# pcb_pedale_test-H743-TLV320AIC23B.net
KiCad netlist of a schematic drawn in EAGLE
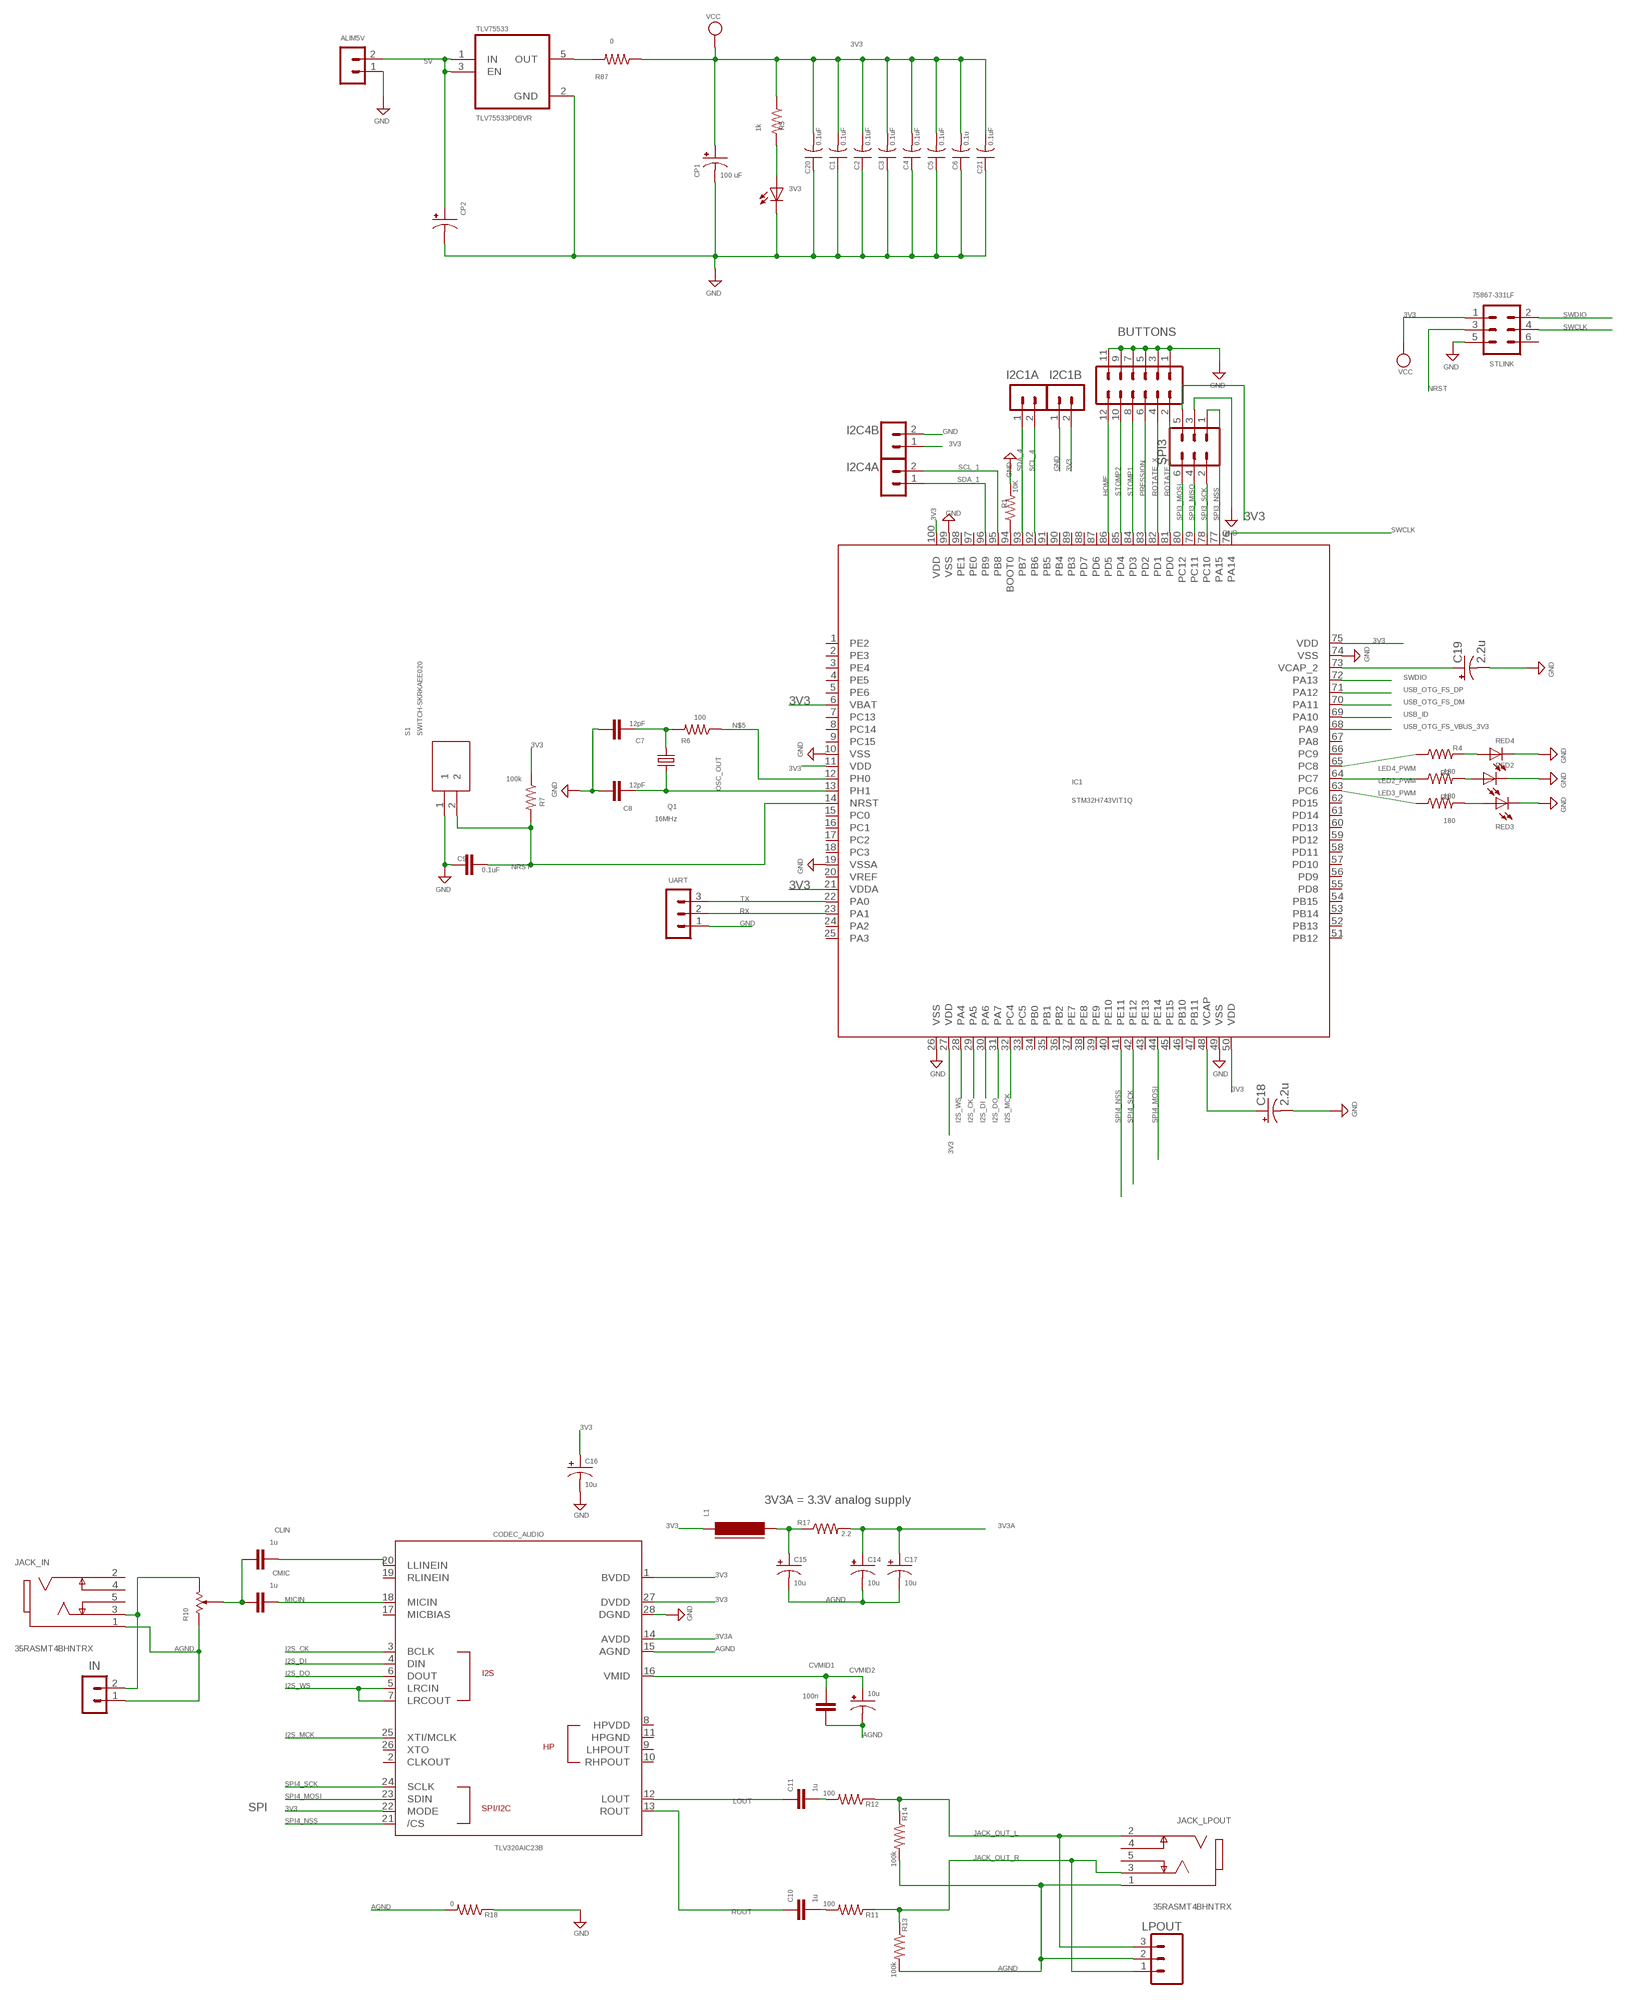
[diagram p0: schematic, sheet 1, part 1 of 2]
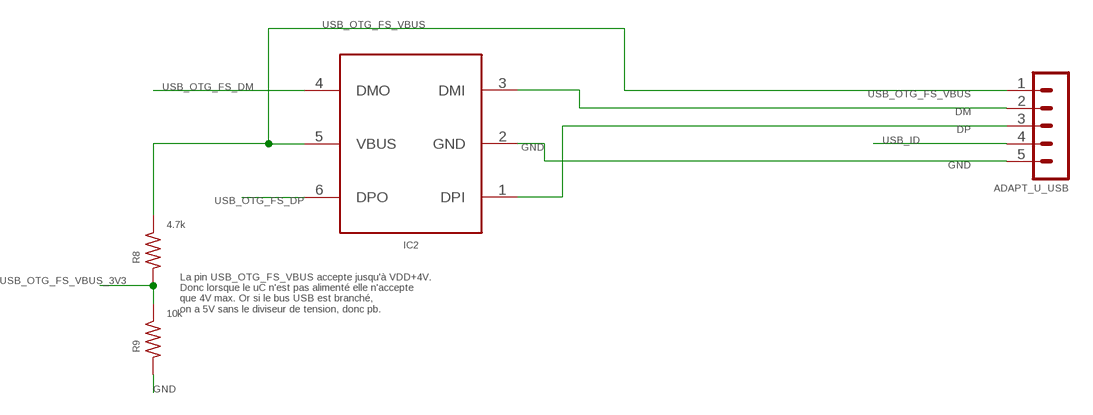
[diagram p1: schematic, sheet 1, part 2 of 2]

(export (version "E")
  (design (tool "Eeschema 10.0.6"))
  (components
    (comp (ref "3V3")
      (value "LED-0805")
      (footprint "eagle-import:0805-LED")
      (libsource (lib "eagle-import") (part "LED-0805"))
    )
    (comp (ref "ADAPT_U_USB")
      (value "MA05-1")
      (footprint "eagle-import:MA05-1")
      (libsource (lib "eagle-import") (part "MA05-1"))
    )
    (comp (ref "ALIM5V")
      (value "MA02-1")
      (footprint "eagle-import:MA02-1")
      (libsource (lib "eagle-import") (part "MA02-1"))
    )
    (comp (ref "BUTTONS")
      (value "MA06-2")
      (footprint "eagle-import:MA06-2")
      (libsource (lib "eagle-import") (part "MA06-2"))
    )
    (comp (ref "C1")
      (value "0.1uF")
      (footprint "eagle-import:C0805")
      (libsource (lib "eagle-import") (part "C-US0805"))
    )
    (comp (ref "C2")
      (value "0.1uF")
      (footprint "eagle-import:C0805")
      (libsource (lib "eagle-import") (part "C-US0805"))
    )
    (comp (ref "C3")
      (value "0.1uF")
      (footprint "eagle-import:C0805")
      (libsource (lib "eagle-import") (part "C-US0805"))
    )
    (comp (ref "C4")
      (value "0.1uF")
      (footprint "eagle-import:C0805")
      (libsource (lib "eagle-import") (part "C-US0805"))
    )
    (comp (ref "C5")
      (value "0.1uF")
      (footprint "eagle-import:C0805")
      (libsource (lib "eagle-import") (part "C-US0805"))
    )
    (comp (ref "C6")
      (value "0.1u")
      (footprint "eagle-import:C0805")
      (libsource (lib "eagle-import") (part "C-US0805"))
    )
    (comp (ref "C7")
      (value "12pF")
      (footprint "eagle-import:1206")
      (libsource (lib "eagle-import") (part "PASSIF-CAP-1206"))
    )
    (comp (ref "C8")
      (value "12pF")
      (footprint "eagle-import:1206")
      (libsource (lib "eagle-import") (part "PASSIF-CAP-1206"))
    )
    (comp (ref "C9")
      (value "0.1uF")
      (footprint "eagle-import:1206")
      (libsource (lib "eagle-import") (part "PASSIF-CAP-1206"))
    )
    (comp (ref "C10")
      (value "1u")
      (footprint "eagle-import:1206")
      (libsource (lib "eagle-import") (part "PASSIF-CAP-1206"))
    )
    (comp (ref "C11")
      (value "1u")
      (footprint "eagle-import:1206")
      (libsource (lib "eagle-import") (part "PASSIF-CAP-1206"))
    )
    (comp (ref "C14")
      (value "10u")
      (footprint "eagle-import:CPOL2917")
      (libsource (lib "eagle-import") (part "PASSIF-CPOL-US2917"))
    )
    (comp (ref "C15")
      (value "10u")
      (footprint "eagle-import:CPOL2917")
      (libsource (lib "eagle-import") (part "PASSIF-CPOL-US2917"))
    )
    (comp (ref "C16")
      (value "10u")
      (footprint "eagle-import:CPOL2917")
      (libsource (lib "eagle-import") (part "PASSIF-CPOL-US2917"))
    )
    (comp (ref "C17")
      (value "10u")
      (footprint "eagle-import:CPOL2917")
      (libsource (lib "eagle-import") (part "PASSIF-CPOL-US2917"))
    )
    (comp (ref "C18")
      (value "2.2u")
      (footprint "eagle-import:CPOL0805")
      (libsource (lib "eagle-import") (part "PASSIF-CPOL-US0805"))
    )
    (comp (ref "C19")
      (value "2.2u")
      (footprint "eagle-import:CPOL0805")
      (libsource (lib "eagle-import") (part "PASSIF-CPOL-US0805"))
    )
    (comp (ref "C20")
      (value "0.1uF")
      (footprint "eagle-import:C0805")
      (libsource (lib "eagle-import") (part "C-US0805"))
    )
    (comp (ref "C21")
      (value "0.1uF")
      (footprint "eagle-import:C0805")
      (libsource (lib "eagle-import") (part "C-US0805"))
    )
    (comp (ref "CLIN")
      (value "1u")
      (footprint "eagle-import:1206")
      (libsource (lib "eagle-import") (part "PASSIF-CAP-1206"))
    )
    (comp (ref "CMIC")
      (value "1u")
      (footprint "eagle-import:1206")
      (libsource (lib "eagle-import") (part "PASSIF-CAP-1206"))
    )
    (comp (ref "CODEC_AUDIO")
      (value "TLV320AIC23B")
      (footprint "eagle-import:TSSOP28")
      (libsource (lib "eagle-import") (part "TLV320AIC23B"))
    )
    (comp (ref "CP1")
      (value "100 uF")
      (footprint "eagle-import:CPOL2917")
      (libsource (lib "eagle-import") (part "CPOL-US2917"))
    )
    (comp (ref "CP2")
      (value "10u")
      (footprint "eagle-import:CPOL2917")
      (libsource (lib "eagle-import") (part "CPOL-US2917"))
    )
    (comp (ref "CVMID1")
      (value "100n")
      (footprint "eagle-import:0805-CAP")
      (libsource (lib "eagle-import") (part "PASSIF-CAP-0805"))
    )
    (comp (ref "CVMID2")
      (value "10u")
      (footprint "eagle-import:CPOL2917")
      (libsource (lib "eagle-import") (part "PASSIF-CPOL-US2917"))
    )
    (comp (ref "I2C1A")
      (value "MA02-1")
      (footprint "eagle-import:MA02-1")
      (libsource (lib "eagle-import") (part "STM32_pi_board_MA02-1"))
    )
    (comp (ref "I2C1B")
      (value "MA02-1")
      (footprint "eagle-import:MA02-1")
      (libsource (lib "eagle-import") (part "STM32_pi_board_MA02-1"))
    )
    (comp (ref "I2C4A")
      (value "MA02-1")
      (footprint "eagle-import:MA02-1")
      (libsource (lib "eagle-import") (part "STM32_pi_board_MA02-1"))
    )
    (comp (ref "I2C4B")
      (value "MA02-1")
      (footprint "eagle-import:MA02-1")
      (libsource (lib "eagle-import") (part "STM32_pi_board_MA02-1"))
    )
    (comp (ref "IC1")
      (value "STM32H743VIT1Q")
      (footprint "eagle-import:LQFP100_14X14")
      (libsource (lib "eagle-import") (part "STM32H743VIT1Q"))
    )
    (comp (ref "IC2")
      (value "STF203-22")
      (footprint "eagle-import:SC70-6")
      (libsource (lib "eagle-import") (part "STF203-22"))
    )
    (comp (ref "IN")
      (value "MA02-1")
      (footprint "eagle-import:MA02-1")
      (libsource (lib "eagle-import") (part "MA02-1"))
    )
    (comp (ref "JACK_IN")
      (value "35RASMT4BHNTRX")
      (footprint "eagle-import:35RASMT4BHNTRX")
      (fields
        (field (name "DIGIKEY_PART_NUMBER") "SC1488-1-ND")
        (field (name "MANUFACTURER") "Switchcraft Inc.")
        (field (name "CREATED_BY") "PCBLayout.com")
      )
      (libsource (lib "eagle-import") (part "35RASMT4BHNTRX"))
    )
    (comp (ref "JACK_LPOUT")
      (value "35RASMT4BHNTRX")
      (footprint "eagle-import:35RASMT4BHNTRX")
      (fields
        (field (name "DIGIKEY_PART_NUMBER") "SC1488-1-ND")
        (field (name "MANUFACTURER") "Switchcraft Inc.")
        (field (name "CREATED_BY") "PCBLayout.com")
      )
      (libsource (lib "eagle-import") (part "35RASMT4BHNTRX"))
    )
    (comp (ref "L1")
      (value "FERRITE-0805")
      (footprint "eagle-import:FB805")
      (libsource (lib "eagle-import") (part "FERRITE-0805"))
    )
    (comp (ref "LPOUT")
      (value "MA03")
      (footprint "eagle-import:03P")
      (libsource (lib "eagle-import") (part "MA03"))
    )
    (comp (ref "Q1")
      (value "16MHz")
      (footprint "eagle-import:Q-HC-46X")
      (libsource (lib "eagle-import") (part "Q-HSEHC-46X"))
    )
    (comp (ref "R1")
      (value "10K")
      (footprint "eagle-import:R0805")
      (libsource (lib "eagle-import") (part "R-US0805"))
    )
    (comp (ref "R2")
      (value "180")
      (footprint "eagle-import:R0805")
      (libsource (lib "eagle-import") (part "R-US0805"))
    )
    (comp (ref "R3")
      (value "180")
      (footprint "eagle-import:R0805")
      (libsource (lib "eagle-import") (part "R-US0805"))
    )
    (comp (ref "R4")
      (value "180")
      (footprint "eagle-import:R0805")
      (libsource (lib "eagle-import") (part "R-US0805"))
    )
    (comp (ref "R5")
      (value "1k")
      (footprint "eagle-import:R0805")
      (libsource (lib "eagle-import") (part "R-US0805"))
    )
    (comp (ref "R6")
      (value "100")
      (footprint "eagle-import:R0805")
      (libsource (lib "eagle-import") (part "R-US0805"))
    )
    (comp (ref "R7")
      (value "100k")
      (footprint "eagle-import:R0805")
      (libsource (lib "eagle-import") (part "R-US0805"))
    )
    (comp (ref "R8")
      (value "4.7k")
      (footprint "eagle-import:R0805")
      (libsource (lib "eagle-import") (part "R-US0805"))
    )
    (comp (ref "R9")
      (value "10k")
      (footprint "eagle-import:R0805")
      (libsource (lib "eagle-import") (part "R-US0805"))
    )
    (comp (ref "R10")
      (value "POTENTIOMETER-PTH")
      (footprint "eagle-import:POT-PTH")
      (libsource (lib "eagle-import") (part "POTENTIOMETER-PTH"))
    )
    (comp (ref "R11")
      (value "100")
      (footprint "eagle-import:R0805")
      (libsource (lib "eagle-import") (part "PASSIF-R-US0805"))
    )
    (comp (ref "R12")
      (value "100")
      (footprint "eagle-import:R0805")
      (libsource (lib "eagle-import") (part "PASSIF-R-US0805"))
    )
    (comp (ref "R13")
      (value "100k")
      (footprint "eagle-import:R0805")
      (libsource (lib "eagle-import") (part "PASSIF-R-US0805"))
    )
    (comp (ref "R14")
      (value "100k")
      (footprint "eagle-import:R0805")
      (libsource (lib "eagle-import") (part "PASSIF-R-US0805"))
    )
    (comp (ref "R17")
      (value "2.2")
      (footprint "eagle-import:R0805")
      (libsource (lib "eagle-import") (part "PASSIF-R-US0805"))
    )
    (comp (ref "R18")
      (value "0")
      (footprint "eagle-import:R0805")
      (libsource (lib "eagle-import") (part "PASSIF-R-US0805"))
    )
    (comp (ref "R87")
      (value "0")
      (footprint "eagle-import:R0805")
      (libsource (lib "eagle-import") (part "R-US0805"))
    )
    (comp (ref "RED2")
      (value "LED3MM")
      (footprint "eagle-import:LED3MM")
      (libsource (lib "eagle-import") (part "LED3MM"))
    )
    (comp (ref "RED3")
      (value "LED3MM")
      (footprint "eagle-import:LED3MM")
      (libsource (lib "eagle-import") (part "LED3MM"))
    )
    (comp (ref "RED4")
      (value "LED-0603")
      (footprint "eagle-import:0603-LED")
      (libsource (lib "eagle-import") (part "LED-0603"))
    )
    (comp (ref "S1")
      (value "SWITCH-SKRKAEE020")
      (footprint "eagle-import:SKRKAEE020")
      (fields
        (field (name "MANUFACTURER_PART_NUMBER") "SKRKAEE020")
        (field (name "MOUSER_PART_NUMBER") "688-SKRKAEE020")
      )
      (libsource (lib "eagle-import") (part "SWITCH-SKRKAEE020"))
    )
    (comp (ref "SPI3")
      (value "MA03-2")
      (footprint "eagle-import:MA03-2")
      (libsource (lib "eagle-import") (part "MA03-2"))
    )
    (comp (ref "STLINK")
      (value "75867-331LF")
      (footprint "eagle-import:MA03-2")
      (libsource (lib "eagle-import") (part "MA03-2"))
    )
    (comp (ref "TLV75533")
      (value "TLV75533PDBVR")
      (footprint "eagle-import:SOT95P280X145-5N")
      (fields (field (name "MF") "Texas Instruments"))
      (libsource (lib "eagle-import") (part "TLV75533PDBVR"))
    )
    (comp (ref "UART")
      (value "MA03-1PL")
      (footprint "eagle-import:MA03-1")
      (libsource (lib "eagle-import") (part "MA03-1PL"))
    )
  )
  (nets
    (net (code "1") (name "/3V3A") (class "Default")
      (node (ref "C14") (pin "+") (pinfunction "+_+") (pintype "passive"))
      (node (ref "C17") (pin "+") (pinfunction "+_+") (pintype "passive"))
      (node (ref "CODEC_AUDIO") (pin "14") (pinfunction "AVDD_14") (pintype "power_in"))
      (node (ref "R17") (pin "2") (pinfunction "2_2") (pintype "passive"))
    )
    (net (code "2") (name "/5V") (class "Default")
      (node (ref "ALIM5V") (pin "2") (pinfunction "2_2") (pintype "passive"))
      (node (ref "CP2") (pin "+") (pinfunction "+_+") (pintype "passive"))
      (node (ref "TLV75533") (pin "1") (pinfunction "IN_1") (pintype "input"))
      (node (ref "TLV75533") (pin "3") (pinfunction "EN_3") (pintype "input"))
    )
    (net (code "3") (name "/AGND") (class "Default")
      (node (ref "C14") (pin "-") (pinfunction "-_-") (pintype "passive"))
      (node (ref "C15") (pin "-") (pinfunction "-_-") (pintype "passive"))
      (node (ref "C17") (pin "-") (pinfunction "-_-") (pintype "passive"))
      (node (ref "CODEC_AUDIO") (pin "15") (pinfunction "AGND_15") (pintype "power_in"))
      (node (ref "CVMID1") (pin "2") (pinfunction "2_2") (pintype "passive"))
      (node (ref "CVMID2") (pin "-") (pinfunction "-_-") (pintype "passive"))
      (node (ref "IN") (pin "1") (pinfunction "1_1") (pintype "passive"))
      (node (ref "JACK_IN") (pin "1") (pinfunction "1_1") (pintype "passive"))
      (node (ref "JACK_LPOUT") (pin "1") (pinfunction "1_1") (pintype "passive"))
      (node (ref "LPOUT") (pin "2") (pinfunction "2_2") (pintype "passive"))
      (node (ref "R10") (pin "3") (pinfunction "3_3") (pintype "passive"))
      (node (ref "R13") (pin "2") (pinfunction "2_2") (pintype "passive"))
      (node (ref "R14") (pin "2") (pinfunction "2_2") (pintype "passive"))
      (node (ref "R18") (pin "2") (pinfunction "2_2") (pintype "passive"))
    )
    (net (code "4") (name "/DM") (class "Default")
      (node (ref "ADAPT_U_USB") (pin "2") (pinfunction "2_2") (pintype "passive"))
      (node (ref "IC2") (pin "3") (pinfunction "DMI_3") (pintype "bidirectional"))
    )
    (net (code "5") (name "/DP") (class "Default")
      (node (ref "ADAPT_U_USB") (pin "3") (pinfunction "3_3") (pintype "passive"))
      (node (ref "IC2") (pin "1") (pinfunction "DPI_1") (pintype "bidirectional"))
    )
    (net (code "6") (name "/HOME") (class "Default")
      (node (ref "BUTTONS") (pin "12") (pinfunction "12_12") (pintype "passive"))
      (node (ref "IC1") (pin "86") (pinfunction "PD5_86") (pintype "bidirectional"))
    )
    (net (code "7") (name "/I2S_CK") (class "Default")
      (node (ref "CODEC_AUDIO") (pin "3") (pinfunction "BCLK_3") (pintype "passive"))
      (node (ref "IC1") (pin "29") (pinfunction "PA5_29") (pintype "bidirectional"))
    )
    (net (code "8") (name "/I2S_DI") (class "Default")
      (node (ref "CODEC_AUDIO") (pin "4") (pinfunction "DIN_4") (pintype "input"))
      (node (ref "IC1") (pin "30") (pinfunction "PA6_30") (pintype "bidirectional"))
    )
    (net (code "9") (name "/I2S_DO") (class "Default")
      (node (ref "CODEC_AUDIO") (pin "6") (pinfunction "DOUT_6") (pintype "input"))
      (node (ref "IC1") (pin "31") (pinfunction "PA7_31") (pintype "bidirectional"))
    )
    (net (code "10") (name "/I2S_MCK") (class "Default")
      (node (ref "CODEC_AUDIO") (pin "25") (pinfunction "XTI/MCLK_25") (pintype "input"))
      (node (ref "IC1") (pin "32") (pinfunction "PC4_32") (pintype "bidirectional"))
    )
    (net (code "11") (name "/I2S_WS") (class "Default")
      (node (ref "CODEC_AUDIO") (pin "5") (pinfunction "LRCIN_5") (pintype "input"))
      (node (ref "CODEC_AUDIO") (pin "7") (pinfunction "LRCOUT_7") (pintype "input"))
      (node (ref "IC1") (pin "28") (pinfunction "PA4_28") (pintype "power_in"))
    )
    (net (code "12") (name "/JACK_OUT_L") (class "Default")
      (node (ref "JACK_LPOUT") (pin "2") (pinfunction "2_2") (pintype "passive"))
      (node (ref "LPOUT") (pin "3") (pinfunction "3_3") (pintype "passive"))
      (node (ref "R12") (pin "1") (pinfunction "1_1") (pintype "passive"))
      (node (ref "R14") (pin "1") (pinfunction "1_1") (pintype "passive"))
    )
    (net (code "13") (name "/JACK_OUT_R") (class "Default")
      (node (ref "JACK_LPOUT") (pin "3") (pinfunction "3_3") (pintype "passive"))
      (node (ref "LPOUT") (pin "1") (pinfunction "1_1") (pintype "passive"))
      (node (ref "R11") (pin "1") (pinfunction "1_1") (pintype "passive"))
      (node (ref "R13") (pin "1") (pinfunction "1_1") (pintype "passive"))
    )
    (net (code "14") (name "/LED2_PWM") (class "Default")
      (node (ref "IC1") (pin "64") (pinfunction "PC7_64") (pintype "bidirectional"))
      (node (ref "R2") (pin "1") (pinfunction "1_1") (pintype "passive"))
    )
    (net (code "15") (name "/LED3_PWM") (class "Default")
      (node (ref "IC1") (pin "63") (pinfunction "PC6_63") (pintype "bidirectional"))
      (node (ref "R3") (pin "1") (pinfunction "1_1") (pintype "passive"))
    )
    (net (code "16") (name "/LED4_PWM") (class "Default")
      (node (ref "IC1") (pin "65") (pinfunction "PC8_65") (pintype "bidirectional"))
      (node (ref "R4") (pin "1") (pinfunction "1_1") (pintype "passive"))
    )
    (net (code "17") (name "/LOUT") (class "Default")
      (node (ref "C11") (pin "1") (pinfunction "1_1") (pintype "passive"))
      (node (ref "CODEC_AUDIO") (pin "12") (pinfunction "LOUT_12") (pintype "output"))
    )
    (net (code "18") (name "/MICIN") (class "Default")
      (node (ref "CMIC") (pin "2") (pinfunction "2_2") (pintype "passive"))
      (node (ref "CODEC_AUDIO") (pin "18") (pinfunction "MICIN_18") (pintype "input"))
    )
    (net (code "19") (name "/N$5") (class "Default")
      (node (ref "IC1") (pin "12") (pinfunction "PH0_12") (pintype "bidirectional"))
      (node (ref "R6") (pin "1") (pinfunction "1_1") (pintype "passive"))
    )
    (net (code "20") (name "/NRST") (class "Default")
      (node (ref "C9") (pin "2") (pinfunction "2_2") (pintype "passive"))
      (node (ref "IC1") (pin "14") (pinfunction "NRST_14") (pintype "input"))
      (node (ref "R7") (pin "2") (pinfunction "2_2") (pintype "passive"))
      (node (ref "S1") (pin "2") (pinfunction "2_2") (pintype "bidirectional"))
      (node (ref "STLINK") (pin "3") (pinfunction "3_3") (pintype "passive"))
    )
    (net (code "21") (name "/OSC_OUT") (class "Default")
      (node (ref "C8") (pin "2") (pinfunction "2_2") (pintype "passive"))
      (node (ref "IC1") (pin "13") (pinfunction "PH1_13") (pintype "bidirectional"))
      (node (ref "Q1") (pin "2") (pinfunction "2_2") (pintype "passive"))
    )
    (net (code "22") (name "/PRESSION") (class "Default")
      (node (ref "BUTTONS") (pin "6") (pinfunction "6_6") (pintype "passive"))
      (node (ref "IC1") (pin "83") (pinfunction "PD2_83") (pintype "bidirectional"))
    )
    (net (code "23") (name "/ROTATE_X") (class "Default")
      (node (ref "BUTTONS") (pin "4") (pinfunction "4_4") (pintype "passive"))
      (node (ref "IC1") (pin "82") (pinfunction "PD1_82") (pintype "bidirectional"))
    )
    (net (code "24") (name "/ROTATE_Y") (class "Default")
      (node (ref "BUTTONS") (pin "2") (pinfunction "2_2") (pintype "passive"))
      (node (ref "IC1") (pin "81") (pinfunction "PD0_81") (pintype "bidirectional"))
    )
    (net (code "25") (name "/ROUT") (class "Default")
      (node (ref "C10") (pin "1") (pinfunction "1_1") (pintype "passive"))
      (node (ref "CODEC_AUDIO") (pin "13") (pinfunction "ROUT_13") (pintype "output"))
    )
    (net (code "26") (name "/RX") (class "Default")
      (node (ref "IC1") (pin "23") (pinfunction "PA1_23") (pintype "bidirectional"))
      (node (ref "UART") (pin "2") (pinfunction "2_2") (pintype "passive"))
    )
    (net (code "27") (name "/SCL_1") (class "Default")
      (node (ref "I2C4A") (pin "2") (pinfunction "2_2") (pintype "passive"))
      (node (ref "IC1") (pin "95") (pinfunction "PB8_95") (pintype "bidirectional"))
    )
    (net (code "28") (name "/SCL_4") (class "Default")
      (node (ref "I2C1A") (pin "2") (pinfunction "2_2") (pintype "passive"))
      (node (ref "IC1") (pin "92") (pinfunction "PB6_92") (pintype "bidirectional"))
    )
    (net (code "29") (name "/SDA_1") (class "Default")
      (node (ref "I2C4A") (pin "1") (pinfunction "1_1") (pintype "passive"))
      (node (ref "IC1") (pin "96") (pinfunction "PB9_96") (pintype "bidirectional"))
    )
    (net (code "30") (name "/SDA_4") (class "Default")
      (node (ref "I2C1A") (pin "1") (pinfunction "1_1") (pintype "passive"))
      (node (ref "IC1") (pin "93") (pinfunction "PB7_93") (pintype "bidirectional"))
    )
    (net (code "31") (name "/SPI3_MISO") (class "Default")
      (node (ref "IC1") (pin "79") (pinfunction "PC11_79") (pintype "bidirectional"))
      (node (ref "SPI3") (pin "4") (pinfunction "4_4") (pintype "passive"))
    )
    (net (code "32") (name "/SPI3_MOSI") (class "Default")
      (node (ref "IC1") (pin "80") (pinfunction "PC12_80") (pintype "bidirectional"))
      (node (ref "SPI3") (pin "6") (pinfunction "6_6") (pintype "passive"))
    )
    (net (code "33") (name "/SPI3_NSS") (class "Default")
      (node (ref "IC1") (pin "77") (pinfunction "PA15_77") (pintype "input"))
      (node (ref "SPI3") (pin "1") (pinfunction "1_1") (pintype "passive"))
    )
    (net (code "34") (name "/SPI3_SCK") (class "Default")
      (node (ref "IC1") (pin "78") (pinfunction "PC10_78") (pintype "bidirectional"))
      (node (ref "SPI3") (pin "2") (pinfunction "2_2") (pintype "passive"))
    )
    (net (code "35") (name "/SPI4_MOSI") (class "Default")
      (node (ref "CODEC_AUDIO") (pin "23") (pinfunction "SDIN_23") (pintype "input"))
      (node (ref "IC1") (pin "44") (pinfunction "PE14_44") (pintype "bidirectional"))
    )
    (net (code "36") (name "/SPI4_NSS") (class "Default")
      (node (ref "CODEC_AUDIO") (pin "21") (pinfunction "/CS_21") (pintype "passive"))
      (node (ref "IC1") (pin "41") (pinfunction "PE11_41") (pintype "bidirectional"))
    )
    (net (code "37") (name "/SPI4_SCK") (class "Default")
      (node (ref "CODEC_AUDIO") (pin "24") (pinfunction "SCLK_24") (pintype "input"))
      (node (ref "IC1") (pin "42") (pinfunction "PE12_42") (pintype "bidirectional"))
    )
    (net (code "38") (name "/STOMP1") (class "Default")
      (node (ref "BUTTONS") (pin "8") (pinfunction "8_8") (pintype "passive"))
      (node (ref "IC1") (pin "84") (pinfunction "PD3_84") (pintype "bidirectional"))
    )
    (net (code "39") (name "/STOMP2") (class "Default")
      (node (ref "BUTTONS") (pin "10") (pinfunction "10_10") (pintype "passive"))
      (node (ref "IC1") (pin "85") (pinfunction "PD4_85") (pintype "bidirectional"))
    )
    (net (code "40") (name "/SWCLK") (class "Default")
      (node (ref "IC1") (pin "76") (pinfunction "PA14_76") (pintype "input"))
      (node (ref "STLINK") (pin "4") (pinfunction "4_4") (pintype "passive"))
    )
    (net (code "41") (name "/SWDIO") (class "Default")
      (node (ref "IC1") (pin "72") (pinfunction "PA13_72") (pintype "input"))
      (node (ref "STLINK") (pin "2") (pinfunction "2_2") (pintype "passive"))
    )
    (net (code "42") (name "/TX") (class "Default")
      (node (ref "IC1") (pin "22") (pinfunction "PA0_22") (pintype "power_in"))
      (node (ref "UART") (pin "3") (pinfunction "3_3") (pintype "passive"))
    )
    (net (code "43") (name "/USB_ID") (class "Default")
      (node (ref "ADAPT_U_USB") (pin "4") (pinfunction "4_4") (pintype "passive"))
      (node (ref "IC1") (pin "69") (pinfunction "PA10_69") (pintype "bidirectional"))
    )
    (net (code "44") (name "/USB_OTG_FS_DM") (class "Default")
      (node (ref "IC1") (pin "70") (pinfunction "PA11_70") (pintype "bidirectional"))
      (node (ref "IC2") (pin "4") (pinfunction "DMO_4") (pintype "bidirectional"))
    )
    (net (code "45") (name "/USB_OTG_FS_DP") (class "Default")
      (node (ref "IC1") (pin "71") (pinfunction "PA12_71") (pintype "bidirectional"))
      (node (ref "IC2") (pin "6") (pinfunction "DPO_6") (pintype "bidirectional"))
    )
    (net (code "46") (name "/USB_OTG_FS_VBUS") (class "Default")
      (node (ref "ADAPT_U_USB") (pin "1") (pinfunction "1_1") (pintype "passive"))
      (node (ref "IC2") (pin "5") (pinfunction "VBUS_5") (pintype "bidirectional"))
      (node (ref "R8") (pin "1") (pinfunction "1_1") (pintype "passive"))
    )
    (net (code "47") (name "/USB_OTG_FS_VBUS_3V3") (class "Default")
      (node (ref "IC1") (pin "68") (pinfunction "PA9_68") (pintype "bidirectional"))
      (node (ref "R8") (pin "2") (pinfunction "2_2") (pintype "passive"))
      (node (ref "R9") (pin "1") (pinfunction "1_1") (pintype "passive"))
    )
    (net (code "48") (name "GND") (class "Default")
      (node (ref "3V3") (pin "C") (pinfunction "C_C") (pintype "passive"))
      (node (ref "ADAPT_U_USB") (pin "5") (pinfunction "5_5") (pintype "passive"))
      (node (ref "ALIM5V") (pin "1") (pinfunction "1_1") (pintype "passive"))
      (node (ref "BUTTONS") (pin "1") (pinfunction "1_1") (pintype "passive"))
      (node (ref "BUTTONS") (pin "11") (pinfunction "11_11") (pintype "passive"))
      (node (ref "BUTTONS") (pin "3") (pinfunction "3_3") (pintype "passive"))
      (node (ref "BUTTONS") (pin "5") (pinfunction "5_5") (pintype "passive"))
      (node (ref "BUTTONS") (pin "7") (pinfunction "7_7") (pintype "passive"))
      (node (ref "BUTTONS") (pin "9") (pinfunction "9_9") (pintype "passive"))
      (node (ref "C1") (pin "1") (pinfunction "1_1") (pintype "passive"))
      (node (ref "C16") (pin "-") (pinfunction "-_-") (pintype "passive"))
      (node (ref "C18") (pin "2-") (pinfunction "-_2-") (pintype "passive"))
      (node (ref "C19") (pin "2-") (pinfunction "-_2-") (pintype "passive"))
      (node (ref "C2") (pin "1") (pinfunction "1_1") (pintype "passive"))
      (node (ref "C20") (pin "1") (pinfunction "1_1") (pintype "passive"))
      (node (ref "C21") (pin "1") (pinfunction "1_1") (pintype "passive"))
      (node (ref "C3") (pin "1") (pinfunction "1_1") (pintype "passive"))
      (node (ref "C4") (pin "1") (pinfunction "1_1") (pintype "passive"))
      (node (ref "C5") (pin "1") (pinfunction "1_1") (pintype "passive"))
      (node (ref "C6") (pin "1") (pinfunction "1_1") (pintype "passive"))
      (node (ref "C7") (pin "1") (pinfunction "1_1") (pintype "passive"))
      (node (ref "C8") (pin "1") (pinfunction "1_1") (pintype "passive"))
      (node (ref "C9") (pin "1") (pinfunction "1_1") (pintype "passive"))
      (node (ref "CODEC_AUDIO") (pin "28") (pinfunction "DGND_28") (pintype "power_in"))
      (node (ref "CP1") (pin "-") (pinfunction "-_-") (pintype "passive"))
      (node (ref "CP2") (pin "-") (pinfunction "-_-") (pintype "passive"))
      (node (ref "I2C1B") (pin "1") (pinfunction "1_1") (pintype "passive"))
      (node (ref "I2C4B") (pin "2") (pinfunction "2_2") (pintype "passive"))
      (node (ref "IC1") (pin "10") (pinfunction "VSS_10") (pintype "power_in"))
      (node (ref "IC1") (pin "19") (pinfunction "VSSA_19") (pintype "power_in"))
      (node (ref "IC1") (pin "26") (pinfunction "VSS_26") (pintype "bidirectional"))
      (node (ref "IC1") (pin "49") (pinfunction "VSS_49") (pintype "power_in"))
      (node (ref "IC1") (pin "74") (pinfunction "VSS_74") (pintype "power_in"))
      (node (ref "IC1") (pin "99") (pinfunction "VSS_99") (pintype "power_in"))
      (node (ref "IC2") (pin "2") (pinfunction "GND_2") (pintype "bidirectional"))
      (node (ref "R1") (pin "2") (pinfunction "2_2") (pintype "passive"))
      (node (ref "R18") (pin "1") (pinfunction "1_1") (pintype "passive"))
      (node (ref "R9") (pin "2") (pinfunction "2_2") (pintype "passive"))
      (node (ref "RED2") (pin "K") (pinfunction "C_K") (pintype "passive"))
      (node (ref "RED3") (pin "K") (pinfunction "C_K") (pintype "passive"))
      (node (ref "RED4") (pin "C") (pinfunction "C_C") (pintype "passive"))
      (node (ref "S1") (pin "1") (pinfunction "1_1") (pintype "bidirectional"))
      (node (ref "SPI3") (pin "3") (pinfunction "3_3") (pintype "passive"))
      (node (ref "STLINK") (pin "5") (pinfunction "5_5") (pintype "passive"))
      (node (ref "TLV75533") (pin "2") (pinfunction "GND_2") (pintype "power_in"))
      (node (ref "UART") (pin "1") (pinfunction "1_1") (pintype "passive"))
    )
    (net (code "49") (name "Net-(3V3-PadA)") (class "Default")
      (node (ref "3V3") (pin "A") (pinfunction "A_A") (pintype "passive"))
      (node (ref "R5") (pin "2") (pinfunction "2_2") (pintype "passive"))
    )
    (net (code "50") (name "Net-(C7-Pad2)") (class "Default")
      (node (ref "C7") (pin "2") (pinfunction "2_2") (pintype "passive"))
      (node (ref "Q1") (pin "1") (pinfunction "1_1") (pintype "passive"))
      (node (ref "R6") (pin "2") (pinfunction "2_2") (pintype "passive"))
    )
    (net (code "51") (name "Net-(C10-Pad2)") (class "Default")
      (node (ref "C10") (pin "2") (pinfunction "2_2") (pintype "passive"))
      (node (ref "R11") (pin "2") (pinfunction "2_2") (pintype "passive"))
    )
    (net (code "52") (name "Net-(C11-Pad2)") (class "Default")
      (node (ref "C11") (pin "2") (pinfunction "2_2") (pintype "passive"))
      (node (ref "R12") (pin "2") (pinfunction "2_2") (pintype "passive"))
    )
    (net (code "53") (name "Net-(C15-Pad+)") (class "Default")
      (node (ref "C15") (pin "+") (pinfunction "+_+") (pintype "passive"))
      (node (ref "L1") (pin "2") (pinfunction "2_2") (pintype "passive"))
      (node (ref "R17") (pin "1") (pinfunction "1_1") (pintype "passive"))
    )
    (net (code "54") (name "Net-(C18-+)") (class "Default")
      (node (ref "C18") (pin "1+") (pinfunction "+_1+") (pintype "passive"))
      (node (ref "IC1") (pin "48") (pinfunction "VCAP_48") (pintype "bidirectional"))
    )
    (net (code "55") (name "Net-(C19-+)") (class "Default")
      (node (ref "C19") (pin "1+") (pinfunction "+_1+") (pintype "passive"))
      (node (ref "IC1") (pin "73") (pinfunction "VCAP_2_73") (pintype "bidirectional"))
    )
    (net (code "56") (name "Net-(CLIN-Pad1)") (class "Default")
      (node (ref "CLIN") (pin "1") (pinfunction "1_1") (pintype "passive"))
      (node (ref "CMIC") (pin "1") (pinfunction "1_1") (pintype "passive"))
      (node (ref "R10") (pin "2") (pinfunction "2_2") (pintype "passive"))
    )
    (net (code "57") (name "Net-(CODEC_AUDIO-LLINEIN)") (class "Default")
      (node (ref "CLIN") (pin "2") (pinfunction "2_2") (pintype "passive"))
      (node (ref "CODEC_AUDIO") (pin "20") (pinfunction "LLINEIN_20") (pintype "input"))
    )
    (net (code "58") (name "Net-(CODEC_AUDIO-VMID)") (class "Default")
      (node (ref "CODEC_AUDIO") (pin "16") (pinfunction "VMID_16") (pintype "input"))
      (node (ref "CVMID1") (pin "1") (pinfunction "1_1") (pintype "passive"))
      (node (ref "CVMID2") (pin "+") (pinfunction "+_+") (pintype "passive"))
    )
    (net (code "59") (name "Net-(IC1-BOOT0)") (class "Default")
      (node (ref "IC1") (pin "94") (pinfunction "BOOT0_94") (pintype "input"))
      (node (ref "R1") (pin "1") (pinfunction "1_1") (pintype "passive"))
    )
    (net (code "60") (name "Net-(IN-Pad2)") (class "Default")
      (node (ref "IN") (pin "2") (pinfunction "2_2") (pintype "passive"))
      (node (ref "JACK_IN") (pin "3") (pinfunction "3_3") (pintype "passive"))
      (node (ref "R10") (pin "1") (pinfunction "1_1") (pintype "passive"))
    )
    (net (code "61") (name "Net-(R2-Pad2)") (class "Default")
      (node (ref "R2") (pin "2") (pinfunction "2_2") (pintype "passive"))
      (node (ref "RED2") (pin "A") (pinfunction "A_A") (pintype "passive"))
    )
    (net (code "62") (name "Net-(R3-Pad2)") (class "Default")
      (node (ref "R3") (pin "2") (pinfunction "2_2") (pintype "passive"))
      (node (ref "RED3") (pin "A") (pinfunction "A_A") (pintype "passive"))
    )
    (net (code "63") (name "Net-(R4-Pad2)") (class "Default")
      (node (ref "R4") (pin "2") (pinfunction "2_2") (pintype "passive"))
      (node (ref "RED4") (pin "A") (pinfunction "A_A") (pintype "passive"))
    )
    (net (code "64") (name "Net-(TLV75533-OUT)") (class "Default")
      (node (ref "R87") (pin "2") (pinfunction "2_2") (pintype "passive"))
      (node (ref "TLV75533") (pin "5") (pinfunction "OUT_5") (pintype "output"))
    )
    (net (code "65") (name "VCC") (class "Default")
      (node (ref "C1") (pin "2") (pinfunction "2_2") (pintype "passive"))
      (node (ref "C16") (pin "+") (pinfunction "+_+") (pintype "passive"))
      (node (ref "C2") (pin "2") (pinfunction "2_2") (pintype "passive"))
      (node (ref "C20") (pin "2") (pinfunction "2_2") (pintype "passive"))
      (node (ref "C21") (pin "2") (pinfunction "2_2") (pintype "passive"))
      (node (ref "C3") (pin "2") (pinfunction "2_2") (pintype "passive"))
      (node (ref "C4") (pin "2") (pinfunction "2_2") (pintype "passive"))
      (node (ref "C5") (pin "2") (pinfunction "2_2") (pintype "passive"))
      (node (ref "C6") (pin "2") (pinfunction "2_2") (pintype "passive"))
      (node (ref "CODEC_AUDIO") (pin "1") (pinfunction "BVDD_1") (pintype "power_in"))
      (node (ref "CODEC_AUDIO") (pin "22") (pinfunction "MODE_22") (pintype "input"))
      (node (ref "CODEC_AUDIO") (pin "27") (pinfunction "DVDD_27") (pintype "power_in"))
      (node (ref "CP1") (pin "+") (pinfunction "+_+") (pintype "passive"))
      (node (ref "I2C1B") (pin "2") (pinfunction "2_2") (pintype "passive"))
      (node (ref "I2C4B") (pin "1") (pinfunction "1_1") (pintype "passive"))
      (node (ref "IC1") (pin "100") (pinfunction "VDD_100") (pintype "power_in"))
      (node (ref "IC1") (pin "11") (pinfunction "VDD_11") (pintype "power_in"))
      (node (ref "IC1") (pin "21") (pinfunction "VDDA_21") (pintype "passive"))
      (node (ref "IC1") (pin "27") (pinfunction "VDD_27") (pintype "power_in"))
      (node (ref "IC1") (pin "50") (pinfunction "VDD_50") (pintype "power_in"))
      (node (ref "IC1") (pin "6") (pinfunction "VBAT_6") (pintype "passive"))
      (node (ref "IC1") (pin "75") (pinfunction "VDD_75") (pintype "power_in"))
      (node (ref "L1") (pin "1") (pinfunction "1_1") (pintype "passive"))
      (node (ref "R5") (pin "1") (pinfunction "1_1") (pintype "passive"))
      (node (ref "R7") (pin "1") (pinfunction "1_1") (pintype "passive"))
      (node (ref "R87") (pin "1") (pinfunction "1_1") (pintype "passive"))
      (node (ref "SPI3") (pin "5") (pinfunction "5_5") (pintype "passive"))
      (node (ref "STLINK") (pin "1") (pinfunction "1_1") (pintype "passive"))
    )
    (net (code "66") (name "unconnected-(CODEC_AUDIO-CLKOUT-Pad2)") (class "Default")
      (node (ref "CODEC_AUDIO") (pin "2") (pinfunction "CLKOUT_2") (pintype "passive"))
    )
    (net (code "67") (name "unconnected-(CODEC_AUDIO-HPGND-Pad11)") (class "Default")
      (node (ref "CODEC_AUDIO") (pin "11") (pinfunction "HPGND_11") (pintype "passive"))
    )
    (net (code "68") (name "unconnected-(CODEC_AUDIO-HPVDD-Pad8)") (class "Default")
      (node (ref "CODEC_AUDIO") (pin "8") (pinfunction "HPVDD_8") (pintype "passive"))
    )
    (net (code "69") (name "unconnected-(CODEC_AUDIO-LHPOUT-Pad9)") (class "Default")
      (node (ref "CODEC_AUDIO") (pin "9") (pinfunction "LHPOUT_9") (pintype "passive"))
    )
    (net (code "70") (name "unconnected-(CODEC_AUDIO-MICBIAS-Pad17)") (class "Default")
      (node (ref "CODEC_AUDIO") (pin "17") (pinfunction "MICBIAS_17") (pintype "input"))
    )
    (net (code "71") (name "unconnected-(CODEC_AUDIO-RHPOUT-Pad10)") (class "Default")
      (node (ref "CODEC_AUDIO") (pin "10") (pinfunction "RHPOUT_10") (pintype "passive"))
    )
    (net (code "72") (name "unconnected-(CODEC_AUDIO-RLINEIN-Pad19)") (class "Default")
      (node (ref "CODEC_AUDIO") (pin "19") (pinfunction "RLINEIN_19") (pintype "input"))
    )
    (net (code "73") (name "unconnected-(CODEC_AUDIO-XTO-Pad26)") (class "Default")
      (node (ref "CODEC_AUDIO") (pin "26") (pinfunction "XTO_26") (pintype "input"))
    )
    (net (code "74") (name "unconnected-(IC1-PA2-Pad24)") (class "Default")
      (node (ref "IC1") (pin "24") (pinfunction "PA2_24") (pintype "bidirectional"))
    )
    (net (code "75") (name "unconnected-(IC1-PA3-Pad25)") (class "Default")
      (node (ref "IC1") (pin "25") (pinfunction "PA3_25") (pintype "bidirectional"))
    )
    (net (code "76") (name "unconnected-(IC1-PA8-Pad67)") (class "Default")
      (node (ref "IC1") (pin "67") (pinfunction "PA8_67") (pintype "bidirectional"))
    )
    (net (code "77") (name "unconnected-(IC1-PB0-Pad34)") (class "Default")
      (node (ref "IC1") (pin "34") (pinfunction "PB0_34") (pintype "bidirectional"))
    )
    (net (code "78") (name "unconnected-(IC1-PB1-Pad35)") (class "Default")
      (node (ref "IC1") (pin "35") (pinfunction "PB1_35") (pintype "bidirectional"))
    )
    (net (code "79") (name "unconnected-(IC1-PB2-Pad36)") (class "Default")
      (node (ref "IC1") (pin "36") (pinfunction "PB2_36") (pintype "bidirectional"))
    )
    (net (code "80") (name "unconnected-(IC1-PB3-Pad89)") (class "Default")
      (node (ref "IC1") (pin "89") (pinfunction "PB3_89") (pintype "output"))
    )
    (net (code "81") (name "unconnected-(IC1-PB4-Pad90)") (class "Default")
      (node (ref "IC1") (pin "90") (pinfunction "PB4_90") (pintype "input"))
    )
    (net (code "82") (name "unconnected-(IC1-PB5-Pad91)") (class "Default")
      (node (ref "IC1") (pin "91") (pinfunction "PB5_91") (pintype "bidirectional"))
    )
    (net (code "83") (name "unconnected-(IC1-PB10-Pad46)") (class "Default")
      (node (ref "IC1") (pin "46") (pinfunction "PB10_46") (pintype "bidirectional"))
    )
    (net (code "84") (name "unconnected-(IC1-PB11-Pad47)") (class "Default")
      (node (ref "IC1") (pin "47") (pinfunction "PB11_47") (pintype "bidirectional"))
    )
    (net (code "85") (name "unconnected-(IC1-PB12-Pad51)") (class "Default")
      (node (ref "IC1") (pin "51") (pinfunction "PB12_51") (pintype "bidirectional"))
    )
    (net (code "86") (name "unconnected-(IC1-PB13-Pad52)") (class "Default")
      (node (ref "IC1") (pin "52") (pinfunction "PB13_52") (pintype "bidirectional"))
    )
    (net (code "87") (name "unconnected-(IC1-PB14-Pad53)") (class "Default")
      (node (ref "IC1") (pin "53") (pinfunction "PB14_53") (pintype "bidirectional"))
    )
    (net (code "88") (name "unconnected-(IC1-PB15-Pad54)") (class "Default")
      (node (ref "IC1") (pin "54") (pinfunction "PB15_54") (pintype "bidirectional"))
    )
    (net (code "89") (name "unconnected-(IC1-PC0-Pad15)") (class "Default")
      (node (ref "IC1") (pin "15") (pinfunction "PC0_15") (pintype "bidirectional"))
    )
    (net (code "90") (name "unconnected-(IC1-PC1-Pad16)") (class "Default")
      (node (ref "IC1") (pin "16") (pinfunction "PC1_16") (pintype "bidirectional"))
    )
    (net (code "91") (name "unconnected-(IC1-PC2-Pad17)") (class "Default")
      (node (ref "IC1") (pin "17") (pinfunction "PC2_17") (pintype "bidirectional"))
    )
    (net (code "92") (name "unconnected-(IC1-PC3-Pad18)") (class "Default")
      (node (ref "IC1") (pin "18") (pinfunction "PC3_18") (pintype "bidirectional"))
    )
    (net (code "93") (name "unconnected-(IC1-PC5-Pad33)") (class "Default")
      (node (ref "IC1") (pin "33") (pinfunction "PC5_33") (pintype "bidirectional"))
    )
    (net (code "94") (name "unconnected-(IC1-PC9-Pad66)") (class "Default")
      (node (ref "IC1") (pin "66") (pinfunction "PC9_66") (pintype "bidirectional"))
    )
    (net (code "95") (name "unconnected-(IC1-PC13-Pad7)") (class "Default")
      (node (ref "IC1") (pin "7") (pinfunction "PC13_7") (pintype "bidirectional"))
    )
    (net (code "96") (name "unconnected-(IC1-PC14-Pad8)") (class "Default")
      (node (ref "IC1") (pin "8") (pinfunction "PC14_8") (pintype "bidirectional"))
    )
    (net (code "97") (name "unconnected-(IC1-PC15-Pad9)") (class "Default")
      (node (ref "IC1") (pin "9") (pinfunction "PC15_9") (pintype "bidirectional"))
    )
    (net (code "98") (name "unconnected-(IC1-PD6-Pad87)") (class "Default")
      (node (ref "IC1") (pin "87") (pinfunction "PD6_87") (pintype "bidirectional"))
    )
    (net (code "99") (name "unconnected-(IC1-PD7-Pad88)") (class "Default")
      (node (ref "IC1") (pin "88") (pinfunction "PD7_88") (pintype "bidirectional"))
    )
    (net (code "100") (name "unconnected-(IC1-PD8-Pad55)") (class "Default")
      (node (ref "IC1") (pin "55") (pinfunction "PD8_55") (pintype "bidirectional"))
    )
    (net (code "101") (name "unconnected-(IC1-PD9-Pad56)") (class "Default")
      (node (ref "IC1") (pin "56") (pinfunction "PD9_56") (pintype "bidirectional"))
    )
    (net (code "102") (name "unconnected-(IC1-PD10-Pad57)") (class "Default")
      (node (ref "IC1") (pin "57") (pinfunction "PD10_57") (pintype "bidirectional"))
    )
    (net (code "103") (name "unconnected-(IC1-PD11-Pad58)") (class "Default")
      (node (ref "IC1") (pin "58") (pinfunction "PD11_58") (pintype "bidirectional"))
    )
    (net (code "104") (name "unconnected-(IC1-PD12-Pad59)") (class "Default")
      (node (ref "IC1") (pin "59") (pinfunction "PD12_59") (pintype "bidirectional"))
    )
    (net (code "105") (name "unconnected-(IC1-PD13-Pad60)") (class "Default")
      (node (ref "IC1") (pin "60") (pinfunction "PD13_60") (pintype "bidirectional"))
    )
    (net (code "106") (name "unconnected-(IC1-PD14-Pad61)") (class "Default")
      (node (ref "IC1") (pin "61") (pinfunction "PD14_61") (pintype "bidirectional"))
    )
    (net (code "107") (name "unconnected-(IC1-PD15-Pad62)") (class "Default")
      (node (ref "IC1") (pin "62") (pinfunction "PD15_62") (pintype "bidirectional"))
    )
    (net (code "108") (name "unconnected-(IC1-PE0-Pad97)") (class "Default")
      (node (ref "IC1") (pin "97") (pinfunction "PE0_97") (pintype "bidirectional"))
    )
    (net (code "109") (name "unconnected-(IC1-PE1-Pad98)") (class "Default")
      (node (ref "IC1") (pin "98") (pinfunction "PE1_98") (pintype "bidirectional"))
    )
    (net (code "110") (name "unconnected-(IC1-PE2-Pad1)") (class "Default")
      (node (ref "IC1") (pin "1") (pinfunction "PE2_1") (pintype "bidirectional"))
    )
    (net (code "111") (name "unconnected-(IC1-PE3-Pad2)") (class "Default")
      (node (ref "IC1") (pin "2") (pinfunction "PE3_2") (pintype "bidirectional"))
    )
    (net (code "112") (name "unconnected-(IC1-PE4-Pad3)") (class "Default")
      (node (ref "IC1") (pin "3") (pinfunction "PE4_3") (pintype "bidirectional"))
    )
    (net (code "113") (name "unconnected-(IC1-PE5-Pad4)") (class "Default")
      (node (ref "IC1") (pin "4") (pinfunction "PE5_4") (pintype "bidirectional"))
    )
    (net (code "114") (name "unconnected-(IC1-PE6-Pad5)") (class "Default")
      (node (ref "IC1") (pin "5") (pinfunction "PE6_5") (pintype "bidirectional"))
    )
    (net (code "115") (name "unconnected-(IC1-PE7-Pad37)") (class "Default")
      (node (ref "IC1") (pin "37") (pinfunction "PE7_37") (pintype "bidirectional"))
    )
    (net (code "116") (name "unconnected-(IC1-PE8-Pad38)") (class "Default")
      (node (ref "IC1") (pin "38") (pinfunction "PE8_38") (pintype "bidirectional"))
    )
    (net (code "117") (name "unconnected-(IC1-PE9-Pad39)") (class "Default")
      (node (ref "IC1") (pin "39") (pinfunction "PE9_39") (pintype "bidirectional"))
    )
    (net (code "118") (name "unconnected-(IC1-PE10-Pad40)") (class "Default")
      (node (ref "IC1") (pin "40") (pinfunction "PE10_40") (pintype "bidirectional"))
    )
    (net (code "119") (name "unconnected-(IC1-PE13-Pad43)") (class "Default")
      (node (ref "IC1") (pin "43") (pinfunction "PE13_43") (pintype "bidirectional"))
    )
    (net (code "120") (name "unconnected-(IC1-PE15-Pad45)") (class "Default")
      (node (ref "IC1") (pin "45") (pinfunction "PE15_45") (pintype "bidirectional"))
    )
    (net (code "121") (name "unconnected-(IC1-VREF-Pad20)") (class "Default")
      (node (ref "IC1") (pin "20") (pinfunction "VREF_20") (pintype "passive"))
    )
    (net (code "122") (name "unconnected-(JACK_IN-Pad2)") (class "Default")
      (node (ref "JACK_IN") (pin "2") (pinfunction "2_2") (pintype "passive"))
    )
    (net (code "123") (name "unconnected-(JACK_IN-Pad4)") (class "Default")
      (node (ref "JACK_IN") (pin "4") (pinfunction "4_4") (pintype "passive"))
    )
    (net (code "124") (name "unconnected-(JACK_IN-Pad5)") (class "Default")
      (node (ref "JACK_IN") (pin "5") (pinfunction "5_5") (pintype "passive"))
    )
    (net (code "125") (name "unconnected-(JACK_LPOUT-Pad4)") (class "Default")
      (node (ref "JACK_LPOUT") (pin "4") (pinfunction "4_4") (pintype "passive"))
    )
    (net (code "126") (name "unconnected-(JACK_LPOUT-Pad5)") (class "Default")
      (node (ref "JACK_LPOUT") (pin "5") (pinfunction "5_5") (pintype "passive"))
    )
    (net (code "127") (name "unconnected-(STLINK-Pad6)") (class "Default")
      (node (ref "STLINK") (pin "6") (pinfunction "6_6") (pintype "passive"))
    )
  )
)
